# PERIPHERAL_PORT_IO.net
KiCad netlist of a schematic drawn in Altium Designer
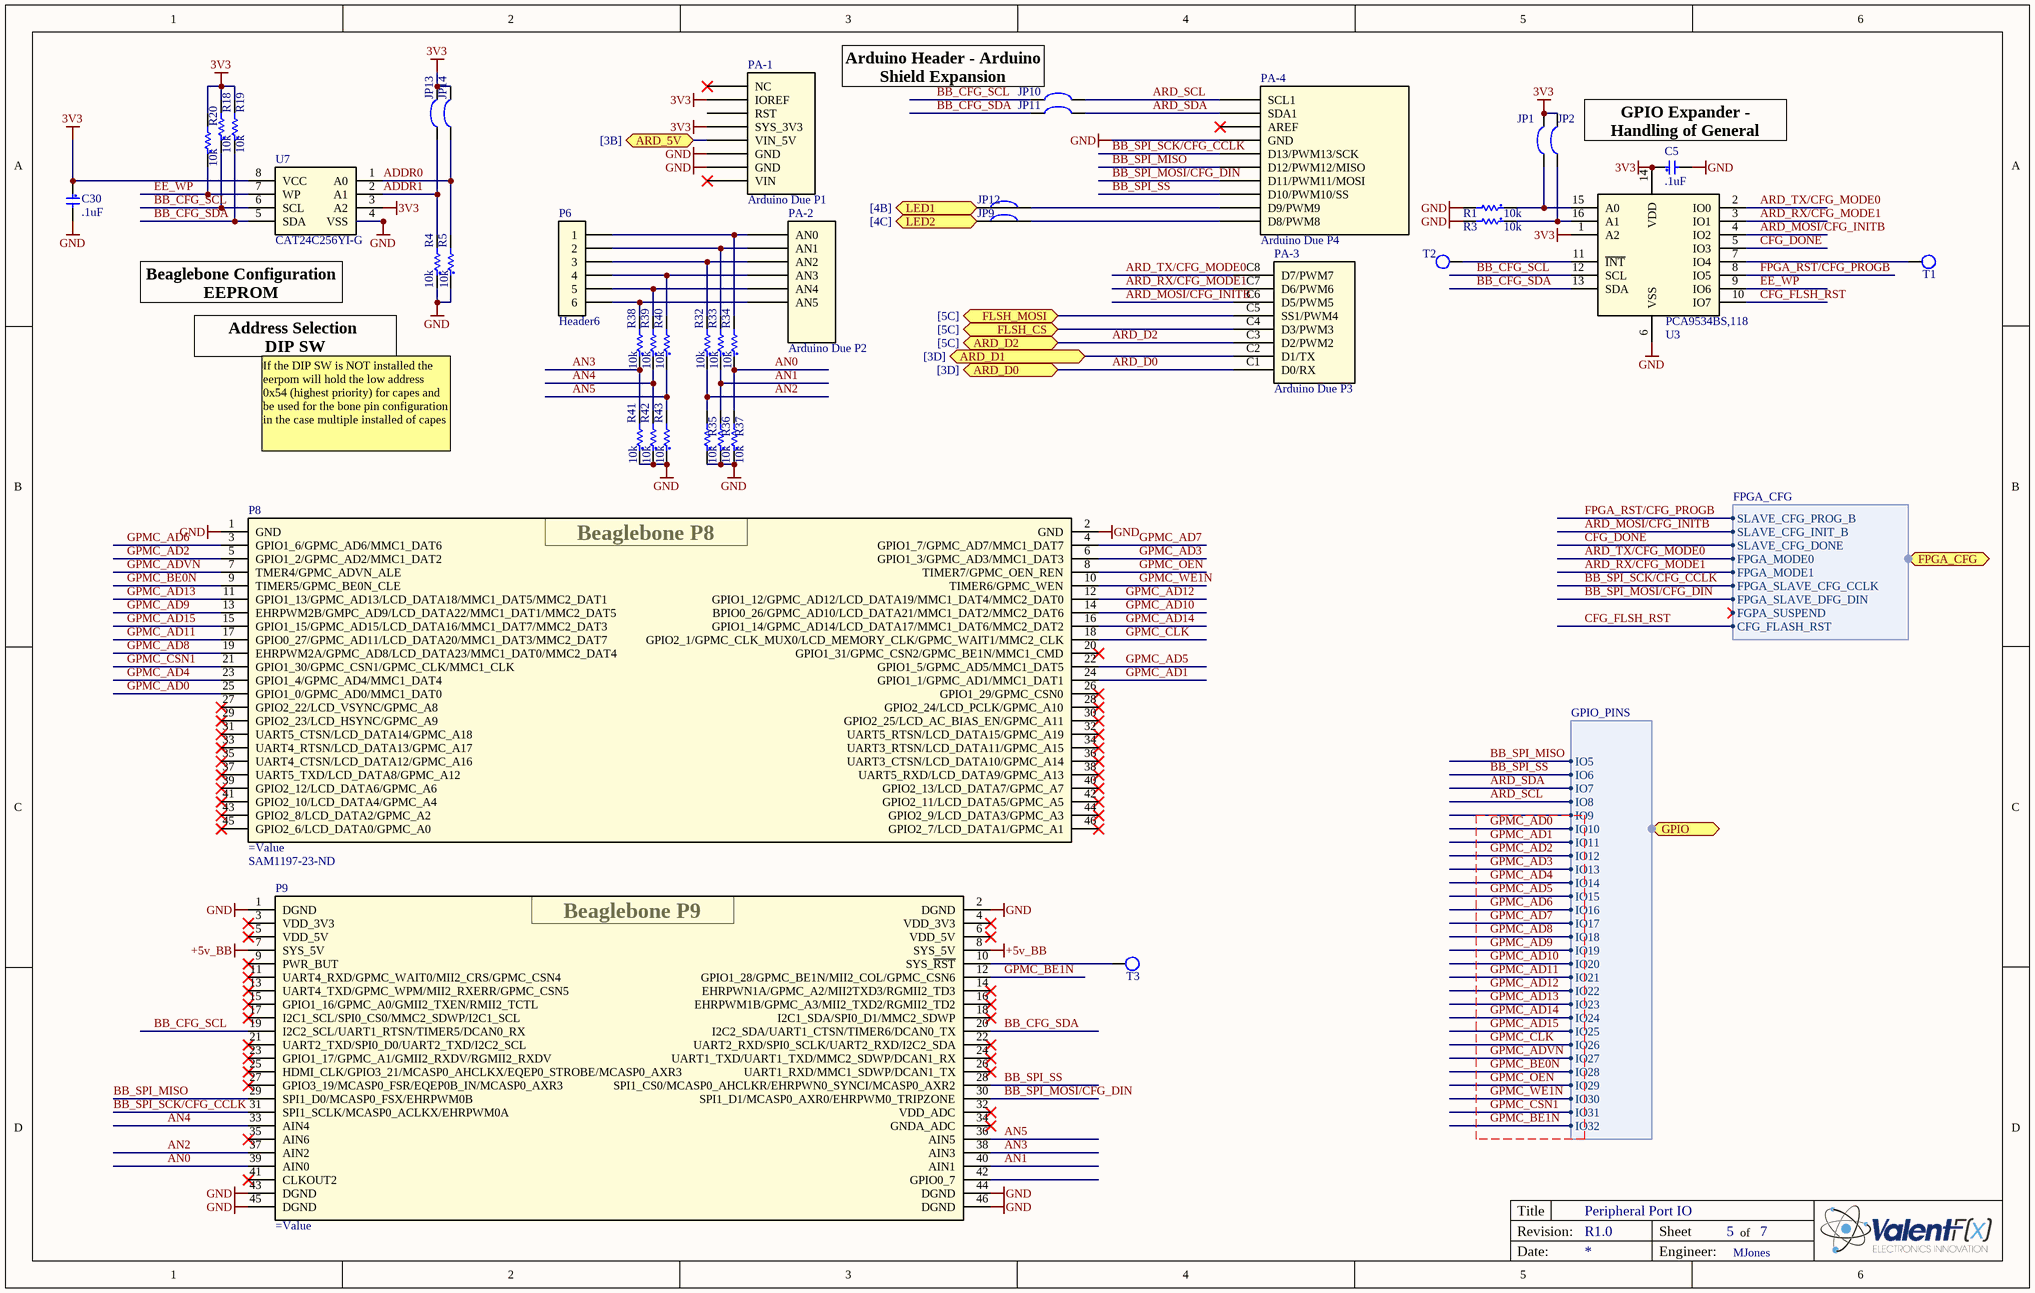
[diagram p0: PERIPHERAL_PORT_IO.SchDoc]

(export (version "E")
  (design (tool "Eeschema 10.0.6"))
  (components
    (comp (ref "C5")
      (value ".1uF")
      (footprint "c0603")
      (description "CAP CER 0.1UF 25V Y5V 0603")
      (fields
        (field (name "MANUFACTURER") "Samsung Electro-Mechanics America, Inc")
        (field (name "MANUFACTURER PART NUMBER") "CL10F104ZA8NNNC")
      )
      (libsource (lib "mCapacitors") (part "C0603 - CL10F104ZA8NNNC"))
    )
    (comp (ref "C30")
      (value ".1uF")
      (footprint "c0603")
      (description "CAP CER 0.1UF 25V Y5V 0603")
      (fields
        (field (name "MANUFACTURER") "Samsung Electro-Mechanics America, Inc")
        (field (name "MANUFACTURER PART NUMBER") "CL10F104ZA8NNNC")
      )
      (libsource (lib "") (part "C0603 - CL10F104ZA8NNNC_1"))
    )
    (comp (ref "JP1")
      (value "Solder Jumper")
      (footprint "SOLDER_JUMPER")
      (description "Solder/Configuration Jumper")
      (fields (field (name "MANUFACTURER") "n/a"))
      (libsource (lib "mConnector") (part "Solder Jumper"))
    )
    (comp (ref "JP2")
      (value "Solder Jumper")
      (footprint "SOLDER_JUMPER")
      (description "Solder/Configuration Jumper")
      (fields (field (name "MANUFACTURER") "n/a"))
      (libsource (lib "mConnector") (part "Solder Jumper"))
    )
    (comp (ref "JP9")
      (value "Solder Jumper-NC")
      (footprint "SOLDER_JUMPER-NC")
      (description "Solder/Configuration Jumper")
      (fields (field (name "MANUFACTURER") "n/a"))
      (libsource (lib "mConnector") (part "Solder Jumper-NC"))
    )
    (comp (ref "JP10")
      (value "Solder Jumper")
      (footprint "SOLDER_JUMPER")
      (description "Solder/Configuration Jumper")
      (fields (field (name "MANUFACTURER") "n/a"))
      (libsource (lib "") (part "Solder Jumper_1"))
    )
    (comp (ref "JP11")
      (value "Solder Jumper")
      (footprint "SOLDER_JUMPER")
      (description "Solder/Configuration Jumper")
      (fields (field (name "MANUFACTURER") "n/a"))
      (libsource (lib "") (part "Solder Jumper_1"))
    )
    (comp (ref "JP12")
      (value "Solder Jumper-NC")
      (footprint "SOLDER_JUMPER-NC")
      (description "Solder/Configuration Jumper")
      (fields (field (name "MANUFACTURER") "n/a"))
      (libsource (lib "mConnector") (part "Solder Jumper-NC"))
    )
    (comp (ref "JP13")
      (value "Solder Jumper")
      (footprint "SOLDER_JUMPER")
      (description "Solder/Configuration Jumper")
      (fields (field (name "MANUFACTURER") "n/a"))
      (libsource (lib "mConnector") (part "Solder Jumper"))
    )
    (comp (ref "JP14")
      (value "Solder Jumper")
      (footprint "SOLDER_JUMPER")
      (description "Solder/Configuration Jumper")
      (fields (field (name "MANUFACTURER") "n/a"))
      (libsource (lib "mConnector") (part "Solder Jumper"))
    )
    (comp (ref "P6")
      (value "Header6")
      (footprint "HEADER_6_40_100 THRU SIP")
      (description "Header 6 pin")
      (libsource (lib "mConnector") (part "Header6"))
    )
    (comp (ref "P8")
      (value "~")
      (footprint "Beaglebone-SSQ")
      (description "Beagle_Bone_Black_P8")
      (fields
        (field (name "MANUFACTURER") "Samtec Inc")
        (field (name "MANUFACTURER PART NUMBER") "SSQ-123-03-G-D-RA")
        (field (name "SUPPLIER PART NUMBER 1") "SAM1197-23-ND")
      )
      (libsource (lib "mConnector") (part "Beagle_Bone_Black_P8-SSQ"))
    )
    (comp (ref "P9")
      (value "~")
      (footprint "Beaglebone-SSQ")
      (description "Beagle_Bone_Black_P9")
      (fields
        (field (name "MANUFACTURER") "Samtec Inc")
        (field (name "MANUFACTURER PART NUMBER") "SSQ-123-03-G-D-RA")
      )
      (libsource (lib "mConnector") (part "Beagle_Bone_Black_P9-SSQ"))
    )
    (comp (ref "PA-1")
      (value "Arduino Due P1")
      (footprint "Arduino Due P1")
      (description "CONN HEADER FEMALE 8POS .1\" GOLD")
      (fields
        (field (name "MANUFACTURER") "Sullins Connector Solutions")
        (field (name "MANUFACTURER PART NUMBER") "PPPC081LFBN-RC")
      )
      (libsource (lib "mConnector") (part "Arduino Due P1"))
    )
    (comp (ref "PA-2")
      (value "Arduino Due P2")
      (footprint "Arduino Due P2")
      (description "CONN HEADER FEMALE 6POS .1\" GOLD")
      (fields
        (field (name "MANUFACTURER") "Sullins Connector Solutions")
        (field (name "MANUFACTURER PART NUMBER") "PPPC061LFBN-RC")
      )
      (libsource (lib "mConnector") (part "Arduino Due P2"))
    )
    (comp (ref "PA-3")
      (value "Arduino Due P3")
      (footprint "Arduino Due P3")
      (description "CONN HEADER FEMALE 8POS .1\" GOLD")
      (fields
        (field (name "MANUFACTURER") "Sullins Connector Solutions")
        (field (name "MANUFACTURER PART NUMBER") "PPPC081LFBN-RC")
      )
      (libsource (lib "mConnector") (part "Arduino Due P3"))
    )
    (comp (ref "PA-4")
      (value "Arduino Due P4")
      (footprint "Arduino Due P4")
      (description "CONN HEADER FMALE 10POS .1\" GOLD")
      (fields
        (field (name "MANUFACTURER") "Sullins Connector Solutions")
        (field (name "MANUFACTURER PART NUMBER") "PPPC101LFBN-RC")
      )
      (libsource (lib "mConnector") (part "Arduino Due P4"))
    )
    (comp (ref "R1")
      (value "10k")
      (footprint "mRCL:R0603")
      (description "10k Thick Film Resistors - SMD 1/10watt 10Kohms 1%")
      (fields
        (field (name "MANUFACTURER") "Vishay Dale")
        (field (name "MANUFACTURER PART NUMBER") "CRCW060310K0FKEA")
      )
      (libsource (lib "mResistors") (part "R0603 - CRCW060310K0FKEA"))
    )
    (comp (ref "R3")
      (value "10k")
      (footprint "mRCL:R0603")
      (description "10k Thick Film Resistors - SMD 1/10watt 10Kohms 1%")
      (fields
        (field (name "MANUFACTURER") "Vishay Dale")
        (field (name "MANUFACTURER PART NUMBER") "CRCW060310K0FKEA")
      )
      (libsource (lib "mResistors") (part "R0603 - CRCW060310K0FKEA"))
    )
    (comp (ref "R4")
      (value "10k")
      (footprint "mRCL:R0603")
      (description "10k Thick Film Resistors - SMD 1/10watt 10Kohms 1%")
      (fields
        (field (name "MANUFACTURER") "Vishay Dale")
        (field (name "MANUFACTURER PART NUMBER") "CRCW060310K0FKEA")
      )
      (libsource (lib "mResistors") (part "R0603 - CRCW060310K0FKEA"))
    )
    (comp (ref "R5")
      (value "10k")
      (footprint "mRCL:R0603")
      (description "10k Thick Film Resistors - SMD 1/10watt 10Kohms 1%")
      (fields
        (field (name "MANUFACTURER") "Vishay Dale")
        (field (name "MANUFACTURER PART NUMBER") "CRCW060310K0FKEA")
      )
      (libsource (lib "mResistors") (part "R0603 - CRCW060310K0FKEA"))
    )
    (comp (ref "R18")
      (value "10k")
      (footprint "mRCL:R0603")
      (description "10k Thick Film Resistors - SMD 1/10watt 10Kohms 1%")
      (fields
        (field (name "MANUFACTURER") "Vishay Dale")
        (field (name "MANUFACTURER PART NUMBER") "CRCW060310K0FKEA")
      )
      (libsource (lib "mResistors") (part "R0603 - CRCW060310K0FKEA"))
    )
    (comp (ref "R19")
      (value "10k")
      (footprint "mRCL:R0603")
      (description "10k Thick Film Resistors - SMD 1/10watt 10Kohms 1%")
      (fields
        (field (name "MANUFACTURER") "Vishay Dale")
        (field (name "MANUFACTURER PART NUMBER") "CRCW060310K0FKEA")
      )
      (libsource (lib "mResistors") (part "R0603 - CRCW060310K0FKEA"))
    )
    (comp (ref "R20")
      (value "10k")
      (footprint "mRCL:R0603")
      (description "10k Thick Film Resistors - SMD 1/10watt 10Kohms 1%")
      (fields
        (field (name "MANUFACTURER") "Vishay Dale")
        (field (name "MANUFACTURER PART NUMBER") "CRCW060310K0FKEA")
      )
      (libsource (lib "mResistors") (part "R0603 - CRCW060310K0FKEA"))
    )
    (comp (ref "R32")
      (value "10k")
      (footprint "mRCL:R0603")
      (description "10k Thick Film Resistors - SMD 1/10watt 10Kohms 1%")
      (fields
        (field (name "MANUFACTURER") "Vishay Dale")
        (field (name "MANUFACTURER PART NUMBER") "CRCW060310K0FKEA")
      )
      (libsource (lib "mResistors") (part "R0603 - CRCW060310K0FKEA"))
    )
    (comp (ref "R33")
      (value "10k")
      (footprint "mRCL:R0603")
      (description "10k Thick Film Resistors - SMD 1/10watt 10Kohms 1%")
      (fields
        (field (name "MANUFACTURER") "Vishay Dale")
        (field (name "MANUFACTURER PART NUMBER") "CRCW060310K0FKEA")
      )
      (libsource (lib "mResistors") (part "R0603 - CRCW060310K0FKEA"))
    )
    (comp (ref "R34")
      (value "10k")
      (footprint "mRCL:R0603")
      (description "10k Thick Film Resistors - SMD 1/10watt 10Kohms 1%")
      (fields
        (field (name "MANUFACTURER") "Vishay Dale")
        (field (name "MANUFACTURER PART NUMBER") "CRCW060310K0FKEA")
      )
      (libsource (lib "mResistors") (part "R0603 - CRCW060310K0FKEA"))
    )
    (comp (ref "R35")
      (value "10k")
      (footprint "mRCL:R0603")
      (description "10k Thick Film Resistors - SMD 1/10watt 10Kohms 1%")
      (fields
        (field (name "MANUFACTURER") "Vishay Dale")
        (field (name "MANUFACTURER PART NUMBER") "CRCW060310K0FKEA")
      )
      (libsource (lib "mResistors") (part "R0603 - CRCW060310K0FKEA"))
    )
    (comp (ref "R36")
      (value "10k")
      (footprint "mRCL:R0603")
      (description "10k Thick Film Resistors - SMD 1/10watt 10Kohms 1%")
      (fields
        (field (name "MANUFACTURER") "Vishay Dale")
        (field (name "MANUFACTURER PART NUMBER") "CRCW060310K0FKEA")
      )
      (libsource (lib "mResistors") (part "R0603 - CRCW060310K0FKEA"))
    )
    (comp (ref "R37")
      (value "10k")
      (footprint "mRCL:R0603")
      (description "10k Thick Film Resistors - SMD 1/10watt 10Kohms 1%")
      (fields
        (field (name "MANUFACTURER") "Vishay Dale")
        (field (name "MANUFACTURER PART NUMBER") "CRCW060310K0FKEA")
      )
      (libsource (lib "mResistors") (part "R0603 - CRCW060310K0FKEA"))
    )
    (comp (ref "R38")
      (value "10k")
      (footprint "mRCL:R0603")
      (description "10k Thick Film Resistors - SMD 1/10watt 10Kohms 1%")
      (fields
        (field (name "MANUFACTURER") "Vishay Dale")
        (field (name "MANUFACTURER PART NUMBER") "CRCW060310K0FKEA")
      )
      (libsource (lib "mResistors") (part "R0603 - CRCW060310K0FKEA"))
    )
    (comp (ref "R39")
      (value "10k")
      (footprint "mRCL:R0603")
      (description "10k Thick Film Resistors - SMD 1/10watt 10Kohms 1%")
      (fields
        (field (name "MANUFACTURER") "Vishay Dale")
        (field (name "MANUFACTURER PART NUMBER") "CRCW060310K0FKEA")
      )
      (libsource (lib "mResistors") (part "R0603 - CRCW060310K0FKEA"))
    )
    (comp (ref "R40")
      (value "10k")
      (footprint "mRCL:R0603")
      (description "10k Thick Film Resistors - SMD 1/10watt 10Kohms 1%")
      (fields
        (field (name "MANUFACTURER") "Vishay Dale")
        (field (name "MANUFACTURER PART NUMBER") "CRCW060310K0FKEA")
      )
      (libsource (lib "mResistors") (part "R0603 - CRCW060310K0FKEA"))
    )
    (comp (ref "R41")
      (value "10k")
      (footprint "mRCL:R0603")
      (description "10k Thick Film Resistors - SMD 1/10watt 10Kohms 1%")
      (fields
        (field (name "MANUFACTURER") "Vishay Dale")
        (field (name "MANUFACTURER PART NUMBER") "CRCW060310K0FKEA")
      )
      (libsource (lib "mResistors") (part "R0603 - CRCW060310K0FKEA"))
    )
    (comp (ref "R42")
      (value "10k")
      (footprint "mRCL:R0603")
      (description "10k Thick Film Resistors - SMD 1/10watt 10Kohms 1%")
      (fields
        (field (name "MANUFACTURER") "Vishay Dale")
        (field (name "MANUFACTURER PART NUMBER") "CRCW060310K0FKEA")
      )
      (libsource (lib "mResistors") (part "R0603 - CRCW060310K0FKEA"))
    )
    (comp (ref "R43")
      (value "10k")
      (footprint "mRCL:R0603")
      (description "10k Thick Film Resistors - SMD 1/10watt 10Kohms 1%")
      (fields
        (field (name "MANUFACTURER") "Vishay Dale")
        (field (name "MANUFACTURER PART NUMBER") "CRCW060310K0FKEA")
      )
      (libsource (lib "mResistors") (part "R0603 - CRCW060310K0FKEA"))
    )
    (comp (ref "T1")
      (value "Test Point")
      (footprint "Tp 25-40")
      (description "Test Point Smaller Symbol")
      (libsource (lib "mConnector") (part "Test Point 2"))
    )
    (comp (ref "T2")
      (value "Test Point")
      (footprint "Tp 25-40")
      (description "Test Point Smaller Symbol")
      (libsource (lib "mConnector") (part "Test Point 2"))
    )
    (comp (ref "T3")
      (value "Test Point")
      (footprint "Tp 25-40")
      (description "Test Point Smaller Symbol")
      (libsource (lib "mConnector") (part "Test Point 2"))
    )
    (comp (ref "U3")
      (value "PCA9534BS,118")
      (footprint "EXP - PCA9534BS,118 - QFN65P400X400X100-16M")
      (description "I/O Expanders, Repeaters & Hubs 8BIT I2C/SMBUS I/O")
      (fields (field (name "MANUFACTURER") "NXP Semiconductors"))
      (libsource (lib "mIC") (part "EXP - PCA9534BS,118"))
    )
    (comp (ref "U7")
      (value "CAT24C256YI-G")
      (footprint "TSSOP 8")
      (description "IC EEPROM 256KBIT 400KHZ 8TSSOP")
      (fields (field (name "MANUFACTURER") "ON Semiconductor"))
      (libsource (lib "mIC") (part "EEPROM - CAT24C256YI-G"))
    )
  )
  (nets
    (net (code "3") (name "+5v_BB") (class "Default")
      (node (ref "P9") (pin "7") (pinfunction "SYS_5V_7") (pintype "passive"))
      (node (ref "P9") (pin "8") (pinfunction "SYS_5V_8") (pintype "passive"))
    )
    (net (code "4") (name "/ADDR0") (class "Default")
      (node (ref "JP14") (pin "1") (pinfunction "1_1") (pintype "passive"))
      (node (ref "R5") (pin "2") (pinfunction "2_2") (pintype "passive"))
      (node (ref "U7") (pin "1") (pinfunction "A0_1") (pintype "passive"))
    )
    (net (code "5") (name "/ADDR1") (class "Default")
      (node (ref "JP13") (pin "1") (pinfunction "1_1") (pintype "passive"))
      (node (ref "R4") (pin "2") (pinfunction "2_2") (pintype "passive"))
      (node (ref "U7") (pin "2") (pinfunction "A1_2") (pintype "passive"))
    )
    (net (code "6") (name "/AN0") (class "Default")
      (node (ref "P9") (pin "39") (pinfunction "AIN0_39") (pintype "passive"))
      (node (ref "R34") (pin "1") (pinfunction "1_1") (pintype "passive"))
      (node (ref "R37") (pin "2") (pinfunction "2_2") (pintype "passive"))
    )
    (net (code "7") (name "/AN1") (class "Default")
      (node (ref "P9") (pin "40") (pinfunction "AIN1_40") (pintype "passive"))
      (node (ref "R33") (pin "1") (pinfunction "1_1") (pintype "passive"))
      (node (ref "R36") (pin "2") (pinfunction "2_2") (pintype "passive"))
    )
    (net (code "8") (name "/AN2") (class "Default")
      (node (ref "P9") (pin "37") (pinfunction "AIN2_37") (pintype "passive"))
      (node (ref "R32") (pin "1") (pinfunction "1_1") (pintype "passive"))
      (node (ref "R35") (pin "2") (pinfunction "2_2") (pintype "passive"))
    )
    (net (code "9") (name "/AN3") (class "Default")
      (node (ref "P9") (pin "38") (pinfunction "AIN3_38") (pintype "passive"))
      (node (ref "R38") (pin "1") (pinfunction "1_1") (pintype "passive"))
      (node (ref "R41") (pin "2") (pinfunction "2_2") (pintype "passive"))
    )
    (net (code "10") (name "/AN4") (class "Default")
      (node (ref "P9") (pin "33") (pinfunction "AIN4_33") (pintype "passive"))
      (node (ref "R39") (pin "1") (pinfunction "1_1") (pintype "passive"))
      (node (ref "R42") (pin "2") (pinfunction "2_2") (pintype "passive"))
    )
    (net (code "11") (name "/AN5") (class "Default")
      (node (ref "P9") (pin "36") (pinfunction "AIN5_36") (pintype "passive"))
      (node (ref "R40") (pin "1") (pinfunction "1_1") (pintype "passive"))
      (node (ref "R43") (pin "2") (pinfunction "2_2") (pintype "passive"))
    )
    (net (code "12") (name "/ARD_5V") (class "Default")
      (node (ref "PA-1") (pin "A5") (pinfunction "VIN_5V_A5") (pintype "passive"))
    )
    (net (code "13") (name "/ARD_D0") (class "Default")
      (node (ref "PA-3") (pin "C1") (pinfunction "D0/RX_C1") (pintype "passive"))
    )
    (net (code "14") (name "/ARD_D1") (class "Default")
      (node (ref "PA-3") (pin "C2") (pinfunction "D1/TX_C2") (pintype "passive"))
    )
    (net (code "15") (name "/ARD_D2") (class "Default")
      (node (ref "PA-3") (pin "C3") (pinfunction "D2/PWM2_C3") (pintype "passive"))
    )
    (net (code "16") (name "/ARD_MOSI{slash}CFG_INITB") (class "Default")
      (node (ref "PA-3") (pin "C6") (pinfunction "D5/PWM5_C6") (pintype "passive"))
      (node (ref "U3") (pin "4") (pinfunction "IO2_4") (pintype "passive"))
    )
    (net (code "17") (name "/ARD_RX{slash}CFG_MODE1") (class "Default")
      (node (ref "PA-3") (pin "C7") (pinfunction "D6/PWM6_C7") (pintype "passive"))
      (node (ref "U3") (pin "3") (pinfunction "IO1_3") (pintype "passive"))
    )
    (net (code "18") (name "/ARD_SCL") (class "Default")
      (node (ref "JP10") (pin "2") (pinfunction "2_2") (pintype "passive"))
      (node (ref "PA-4") (pin "D10") (pinfunction "SCL1_D10") (pintype "passive"))
    )
    (net (code "19") (name "/ARD_SDA") (class "Default")
      (node (ref "JP11") (pin "2") (pinfunction "2_2") (pintype "passive"))
      (node (ref "PA-4") (pin "D9") (pinfunction "SDA1_D9") (pintype "passive"))
    )
    (net (code "20") (name "/ARD_TX{slash}CFG_MODE0") (class "Default")
      (node (ref "PA-3") (pin "C8") (pinfunction "D7/PWM7_C8") (pintype "passive"))
      (node (ref "U3") (pin "2") (pinfunction "IO0_2") (pintype "passive"))
    )
    (net (code "21") (name "/BB_CFG_SCL") (class "Default")
      (node (ref "JP10") (pin "1") (pinfunction "1_1") (pintype "passive"))
      (node (ref "P9") (pin "19") (pinfunction "I2C2_SCL/UART1_RTSN/TIMER5/DCAN0_RX_19") (pintype "passive"))
      (node (ref "R18") (pin "1") (pinfunction "1_1") (pintype "passive"))
      (node (ref "U3") (pin "12") (pinfunction "SCL_12") (pintype "passive"))
      (node (ref "U7") (pin "6") (pinfunction "SCL_6") (pintype "passive"))
    )
    (net (code "22") (name "/BB_CFG_SDA") (class "Default")
      (node (ref "JP11") (pin "1") (pinfunction "1_1") (pintype "passive"))
      (node (ref "P9") (pin "20") (pinfunction "I2C2_SDA/UART1_CTSN/TIMER6/DCAN0_TX_20") (pintype "passive"))
      (node (ref "R19") (pin "1") (pinfunction "1_1") (pintype "passive"))
      (node (ref "U3") (pin "13") (pinfunction "SDA_13") (pintype "passive"))
      (node (ref "U7") (pin "5") (pinfunction "SDA_5") (pintype "passive"))
    )
    (net (code "23") (name "/BB_SPI_MISO") (class "Default")
      (node (ref "P9") (pin "29") (pinfunction "SPI1_D0/MCASP0_FSX/EHRPWM0B_29") (pintype "passive"))
      (node (ref "PA-4") (pin "D5") (pinfunction "D12/PWM12/MISO_D5") (pintype "passive"))
    )
    (net (code "24") (name "/BB_SPI_MOSI{slash}CFG_DIN") (class "Default")
      (node (ref "P9") (pin "30") (pinfunction "SPI1_D1/MCASP0_AXR0/EHRPWM0_TRIPZONE_30") (pintype "passive"))
      (node (ref "PA-4") (pin "D4") (pinfunction "D11/PWM11/MOSI_D4") (pintype "passive"))
    )
    (net (code "25") (name "/BB_SPI_SCK{slash}CFG_CCLK") (class "Default")
      (node (ref "P9") (pin "31") (pinfunction "SPI1_SCLK/MCASP0_ACLKX/EHRPWM0A_31") (pintype "passive"))
      (node (ref "PA-4") (pin "D6") (pinfunction "D13/PWM13/SCK_D6") (pintype "passive"))
    )
    (net (code "26") (name "/BB_SPI_SS") (class "Default")
      (node (ref "P9") (pin "28") (pinfunction "SPI1_CS0/MCASP0_AHCLKR/EHRPWN0_SYNCI/MCASP0_AXR2_28") (pintype "passive"))
      (node (ref "PA-4") (pin "D3") (pinfunction "D10/PWM10/SS_D3") (pintype "passive"))
    )
    (net (code "27") (name "/CFG_DONE") (class "Default")
      (node (ref "U3") (pin "5") (pinfunction "IO3_5") (pintype "passive"))
    )
    (net (code "28") (name "/CFG_FLSH_RST") (class "Default")
      (node (ref "U3") (pin "10") (pinfunction "IO7_10") (pintype "passive"))
    )
    (net (code "29") (name "/EE_WP") (class "Default")
      (node (ref "R20") (pin "1") (pinfunction "1_1") (pintype "passive"))
      (node (ref "U3") (pin "9") (pinfunction "IO6_9") (pintype "passive"))
      (node (ref "U7") (pin "7") (pinfunction "WP_7") (pintype "passive"))
    )
    (net (code "30") (name "/FLSH_CS") (class "Default")
      (node (ref "PA-3") (pin "C4") (pinfunction "D3/PWM3_C4") (pintype "passive"))
    )
    (net (code "31") (name "/FLSH_MOSI") (class "Default")
      (node (ref "PA-3") (pin "C5") (pinfunction "SS1/PWM4_C5") (pintype "passive"))
    )
    (net (code "32") (name "/FPGA_RST{slash}CFG_PROGB") (class "Default")
      (node (ref "U3") (pin "8") (pinfunction "IO5_8") (pintype "passive"))
    )
    (net (code "33") (name "/GPMC_AD0") (class "Default")
      (node (ref "P8") (pin "25") (pinfunction "GPIO1_0/GPMC_AD0/MMC1_DAT0_25") (pintype "passive"))
    )
    (net (code "34") (name "/GPMC_AD1") (class "Default")
      (node (ref "P8") (pin "24") (pinfunction "GPIO1_1/GPMC_AD1/MMC1_DAT1_24") (pintype "passive"))
    )
    (net (code "35") (name "/GPMC_AD2") (class "Default")
      (node (ref "P8") (pin "5") (pinfunction "GPIO1_2/GPMC_AD2/MMC1_DAT2_5") (pintype "passive"))
    )
    (net (code "36") (name "/GPMC_AD3") (class "Default")
      (node (ref "P8") (pin "6") (pinfunction "GPIO1_3/GPMC_AD3/MMC1_DAT3_6") (pintype "passive"))
    )
    (net (code "37") (name "/GPMC_AD4") (class "Default")
      (node (ref "P8") (pin "23") (pinfunction "GPIO1_4/GPMC_AD4/MMC1_DAT4_23") (pintype "passive"))
    )
    (net (code "38") (name "/GPMC_AD5") (class "Default")
      (node (ref "P8") (pin "22") (pinfunction "GPIO1_5/GPMC_AD5/MMC1_DAT5_22") (pintype "passive"))
    )
    (net (code "39") (name "/GPMC_AD6") (class "Default")
      (node (ref "P8") (pin "3") (pinfunction "GPIO1_6/GPMC_AD6/MMC1_DAT6_3") (pintype "passive"))
    )
    (net (code "40") (name "/GPMC_AD7") (class "Default")
      (node (ref "P8") (pin "4") (pinfunction "GPIO1_7/GPMC_AD7/MMC1_DAT7_4") (pintype "passive"))
    )
    (net (code "41") (name "/GPMC_AD8") (class "Default")
      (node (ref "P8") (pin "19") (pinfunction "EHRPWM2A/GPMC_AD8/LCD_DATA23/MMC1_DAT0/MMC2_DAT4_19") (pintype "passive"))
    )
    (net (code "42") (name "/GPMC_AD9") (class "Default")
      (node (ref "P8") (pin "13") (pinfunction "EHRPWM2B/GMPC_AD9/LCD_DATA22/MMC1_DAT1/MMC2_DAT5_13") (pintype "passive"))
    )
    (net (code "43") (name "/GPMC_AD10") (class "Default")
      (node (ref "P8") (pin "14") (pinfunction "BPIO0_26/GPMC_AD10/LCD_DATA21/MMC1_DAT2/MMC2_DAT6_14") (pintype "passive"))
    )
    (net (code "44") (name "/GPMC_AD11") (class "Default")
      (node (ref "P8") (pin "17") (pinfunction "GPIO0_27/GPMC_AD11/LCD_DATA20/MMC1_DAT3/MMC2_DAT7_17") (pintype "passive"))
    )
    (net (code "45") (name "/GPMC_AD12") (class "Default")
      (node (ref "P8") (pin "12") (pinfunction "GPIO1_12/GPMC_AD12/LCD_DATA19/MMC1_DAT4/MMC2_DAT0_12") (pintype "passive"))
    )
    (net (code "46") (name "/GPMC_AD13") (class "Default")
      (node (ref "P8") (pin "11") (pinfunction "GPIO1_13/GPMC_AD13/LCD_DATA18/MMC1_DAT5/MMC2_DAT1_11") (pintype "passive"))
    )
    (net (code "47") (name "/GPMC_AD14") (class "Default")
      (node (ref "P8") (pin "16") (pinfunction "GPIO1_14/GPMC_AD14/LCD_DATA17/MMC1_DAT6/MMC2_DAT2_16") (pintype "passive"))
    )
    (net (code "48") (name "/GPMC_AD15") (class "Default")
      (node (ref "P8") (pin "15") (pinfunction "GPIO1_15/GPMC_AD15/LCD_DATA16/MMC1_DAT7/MMC2_DAT3_15") (pintype "passive"))
    )
    (net (code "49") (name "/GPMC_ADVN") (class "Default")
      (node (ref "P8") (pin "7") (pinfunction "TMER4/GPMC_ADVN_ALE_7") (pintype "passive"))
    )
    (net (code "50") (name "/GPMC_BE0N") (class "Default")
      (node (ref "P8") (pin "9") (pinfunction "TIMER5/GPMC_BE0N_CLE_9") (pintype "passive"))
    )
    (net (code "51") (name "/GPMC_BE1N") (class "Default")
      (node (ref "P9") (pin "12") (pinfunction "GPIO1_28/GPMC_BE1N/MII2_COL/GPMC_CSN6_12") (pintype "passive"))
    )
    (net (code "52") (name "/GPMC_CLK") (class "Default")
      (node (ref "P8") (pin "18") (pinfunction "GPIO2_1/GPMC_CLK_MUX0/LCD_MEMORY_CLK/GPMC_WAIT1/MMC2_CLK_18") (pintype "passive"))
    )
    (net (code "53") (name "/GPMC_CSN1") (class "Default")
      (node (ref "P8") (pin "21") (pinfunction "GPIO1_30/GPMC_CSN1/GPMC_CLK/MMC1_CLK_21") (pintype "passive"))
    )
    (net (code "54") (name "/GPMC_OEN") (class "Default")
      (node (ref "P8") (pin "8") (pinfunction "TIMER7/GPMC_OEN_REN_8") (pintype "passive"))
    )
    (net (code "55") (name "/GPMC_WE1N") (class "Default")
      (node (ref "P8") (pin "10") (pinfunction "TIMER6/GPMC_WEN_10") (pintype "passive"))
    )
    (net (code "56") (name "/LED1") (class "Default")
      (node (ref "JP12") (pin "1") (pinfunction "1_1") (pintype "passive"))
    )
    (net (code "57") (name "/LED2") (class "Default")
      (node (ref "JP9") (pin "1") (pinfunction "1_1") (pintype "passive"))
    )
    (net (code "60") (name "3V3") (class "Default")
      (node (ref "C30") (pin "1") (pinfunction "1_1") (pintype "passive"))
      (node (ref "C5") (pin "1") (pinfunction "1_1") (pintype "passive"))
      (node (ref "JP1") (pin "2") (pinfunction "2_2") (pintype "passive"))
      (node (ref "JP13") (pin "2") (pinfunction "2_2") (pintype "passive"))
      (node (ref "JP14") (pin "2") (pinfunction "2_2") (pintype "passive"))
      (node (ref "JP2") (pin "2") (pinfunction "2_2") (pintype "passive"))
      (node (ref "PA-1") (pin "A2") (pinfunction "IOREF_A2") (pintype "passive"))
      (node (ref "PA-1") (pin "A4") (pinfunction "SYS_3V3_A4") (pintype "passive"))
      (node (ref "R18") (pin "2") (pinfunction "2_2") (pintype "passive"))
      (node (ref "R19") (pin "2") (pinfunction "2_2") (pintype "passive"))
      (node (ref "R20") (pin "2") (pinfunction "2_2") (pintype "passive"))
      (node (ref "U3") (pin "1") (pinfunction "A2_1") (pintype "passive"))
      (node (ref "U3") (pin "14") (pinfunction "VDD_14") (pintype "passive"))
      (node (ref "U7") (pin "3") (pinfunction "A2_3") (pintype "passive"))
      (node (ref "U7") (pin "8") (pinfunction "VCC_8") (pintype "passive"))
    )
    (net (code "61") (name "GND") (class "Default")
      (node (ref "C30") (pin "2") (pinfunction "2_2") (pintype "passive"))
      (node (ref "C5") (pin "2") (pinfunction "2_2") (pintype "passive"))
      (node (ref "P8") (pin "1") (pinfunction "GND_1") (pintype "passive"))
      (node (ref "P8") (pin "2") (pinfunction "GND_2") (pintype "passive"))
      (node (ref "P9") (pin "1") (pinfunction "DGND_1") (pintype "passive"))
      (node (ref "P9") (pin "2") (pinfunction "DGND_2") (pintype "passive"))
      (node (ref "P9") (pin "43") (pinfunction "DGND_43") (pintype "passive"))
      (node (ref "P9") (pin "44") (pinfunction "DGND_44") (pintype "passive"))
      (node (ref "P9") (pin "45") (pinfunction "DGND_45") (pintype "passive"))
      (node (ref "P9") (pin "46") (pinfunction "DGND_46") (pintype "passive"))
      (node (ref "PA-1") (pin "A6") (pinfunction "GND_A6") (pintype "passive"))
      (node (ref "PA-1") (pin "A7") (pinfunction "GND_A7") (pintype "passive"))
      (node (ref "PA-4") (pin "D7") (pinfunction "GND_D7") (pintype "passive"))
      (node (ref "R1") (pin "2") (pinfunction "2_2") (pintype "passive"))
      (node (ref "R3") (pin "2") (pinfunction "2_2") (pintype "passive"))
      (node (ref "R35") (pin "1") (pinfunction "1_1") (pintype "passive"))
      (node (ref "R36") (pin "1") (pinfunction "1_1") (pintype "passive"))
      (node (ref "R37") (pin "1") (pinfunction "1_1") (pintype "passive"))
      (node (ref "R4") (pin "1") (pinfunction "1_1") (pintype "passive"))
      (node (ref "R41") (pin "1") (pinfunction "1_1") (pintype "passive"))
      (node (ref "R42") (pin "1") (pinfunction "1_1") (pintype "passive"))
      (node (ref "R43") (pin "1") (pinfunction "1_1") (pintype "passive"))
      (node (ref "R5") (pin "1") (pinfunction "1_1") (pintype "passive"))
      (node (ref "U3") (pin "6") (pinfunction "VSS_6") (pintype "passive"))
      (node (ref "U7") (pin "4") (pinfunction "VSS_4") (pintype "passive"))
    )
    (net (code "62") (name "Net-(P9-SYS_~{RST})") (class "Default")
      (node (ref "P9") (pin "10") (pinfunction "SYS_~{RST}_10") (pintype "passive"))
      (node (ref "T3") (pin "1") (pinfunction "1_1") (pintype "passive"))
    )
    (net (code "63") (name "Net-(PA-2-AN0)") (class "Default")
      (node (ref "P6") (pin "1") (pinfunction "1_1") (pintype "passive"))
      (node (ref "PA-2") (pin "B1") (pinfunction "AN0_B1") (pintype "passive"))
      (node (ref "R34") (pin "2") (pinfunction "2_2") (pintype "passive"))
    )
    (net (code "64") (name "Net-(PA-2-AN1)") (class "Default")
      (node (ref "P6") (pin "2") (pinfunction "2_2") (pintype "passive"))
      (node (ref "PA-2") (pin "B2") (pinfunction "AN1_B2") (pintype "passive"))
      (node (ref "R33") (pin "2") (pinfunction "2_2") (pintype "passive"))
    )
    (net (code "65") (name "Net-(PA-2-AN2)") (class "Default")
      (node (ref "P6") (pin "3") (pinfunction "3_3") (pintype "passive"))
      (node (ref "PA-2") (pin "B3") (pinfunction "AN2_B3") (pintype "passive"))
      (node (ref "R32") (pin "2") (pinfunction "2_2") (pintype "passive"))
    )
    (net (code "66") (name "Net-(PA-2-AN3)") (class "Default")
      (node (ref "P6") (pin "4") (pinfunction "4_4") (pintype "passive"))
      (node (ref "PA-2") (pin "B4") (pinfunction "AN3_B4") (pintype "passive"))
      (node (ref "R40") (pin "2") (pinfunction "2_2") (pintype "passive"))
    )
    (net (code "67") (name "Net-(PA-2-AN4)") (class "Default")
      (node (ref "P6") (pin "5") (pinfunction "5_5") (pintype "passive"))
      (node (ref "PA-2") (pin "B5") (pinfunction "AN4_B5") (pintype "passive"))
      (node (ref "R39") (pin "2") (pinfunction "2_2") (pintype "passive"))
    )
    (net (code "68") (name "Net-(PA-2-AN5)") (class "Default")
      (node (ref "P6") (pin "6") (pinfunction "6_6") (pintype "passive"))
      (node (ref "PA-2") (pin "B6") (pinfunction "AN5_B6") (pintype "passive"))
      (node (ref "R38") (pin "2") (pinfunction "2_2") (pintype "passive"))
    )
    (net (code "69") (name "Net-(PA-4-D8{slash}PWM8)") (class "Default")
      (node (ref "JP9") (pin "2") (pinfunction "2_2") (pintype "passive"))
      (node (ref "PA-4") (pin "D1") (pinfunction "D8/PWM8_D1") (pintype "passive"))
    )
    (net (code "70") (name "Net-(PA-4-D9{slash}PWM9)") (class "Default")
      (node (ref "JP12") (pin "2") (pinfunction "2_2") (pintype "passive"))
      (node (ref "PA-4") (pin "D2") (pinfunction "D9/PWM9_D2") (pintype "passive"))
    )
    (net (code "71") (name "Net-(U3-A0)") (class "Default")
      (node (ref "JP1") (pin "1") (pinfunction "1_1") (pintype "passive"))
      (node (ref "R1") (pin "1") (pinfunction "1_1") (pintype "passive"))
      (node (ref "U3") (pin "15") (pinfunction "A0_15") (pintype "passive"))
    )
    (net (code "72") (name "Net-(U3-A1)") (class "Default")
      (node (ref "JP2") (pin "1") (pinfunction "1_1") (pintype "passive"))
      (node (ref "R3") (pin "1") (pinfunction "1_1") (pintype "passive"))
      (node (ref "U3") (pin "16") (pinfunction "A1_16") (pintype "passive"))
    )
    (net (code "73") (name "Net-(U3-IO4)") (class "Default")
      (node (ref "T1") (pin "1") (pinfunction "1_1") (pintype "passive"))
      (node (ref "U3") (pin "7") (pinfunction "IO4_7") (pintype "passive"))
    )
    (net (code "74") (name "Net-(U3-~{INT})") (class "Default")
      (node (ref "T2") (pin "1") (pinfunction "1_1") (pintype "passive"))
      (node (ref "U3") (pin "11") (pinfunction "~{INT}_11") (pintype "passive"))
    )
    (net (code "75") (name "unconnected-(P8-GPIO1_29{slash}GPMC_CSN0-Pad26)") (class "Default")
      (node (ref "P8") (pin "26") (pinfunction "GPIO1_29/GPMC_CSN0_26") (pintype "passive+no_connect"))
    )
    (net (code "76") (name "unconnected-(P8-GPIO1_31{slash}GPMC_CSN2{slash}GPMC_BE1N{slash}MMC1_CMD-Pad20)") (class "Default")
      (node (ref "P8") (pin "20") (pinfunction "GPIO1_31/GPMC_CSN2/GPMC_BE1N/MMC1_CMD_20") (pintype "passive+no_connect"))
    )
    (net (code "77") (name "unconnected-(P8-GPIO2_6{slash}LCD_DATA0{slash}GPMC_A0-Pad45)") (class "Default")
      (node (ref "P8") (pin "45") (pinfunction "GPIO2_6/LCD_DATA0/GPMC_A0_45") (pintype "passive+no_connect"))
    )
    (net (code "78") (name "unconnected-(P8-GPIO2_7{slash}LCD_DATA1{slash}GPMC_A1-Pad46)") (class "Default")
      (node (ref "P8") (pin "46") (pinfunction "GPIO2_7/LCD_DATA1/GPMC_A1_46") (pintype "passive+no_connect"))
    )
    (net (code "79") (name "unconnected-(P8-GPIO2_8{slash}LCD_DATA2{slash}GPMC_A2-Pad43)") (class "Default")
      (node (ref "P8") (pin "43") (pinfunction "GPIO2_8/LCD_DATA2/GPMC_A2_43") (pintype "passive+no_connect"))
    )
    (net (code "80") (name "unconnected-(P8-GPIO2_9{slash}LCD_DATA3{slash}GPMC_A3-Pad44)") (class "Default")
      (node (ref "P8") (pin "44") (pinfunction "GPIO2_9/LCD_DATA3/GPMC_A3_44") (pintype "passive+no_connect"))
    )
    (net (code "81") (name "unconnected-(P8-GPIO2_10{slash}LCD_DATA4{slash}GPMC_A4-Pad41)") (class "Default")
      (node (ref "P8") (pin "41") (pinfunction "GPIO2_10/LCD_DATA4/GPMC_A4_41") (pintype "passive+no_connect"))
    )
    (net (code "82") (name "unconnected-(P8-GPIO2_11{slash}LCD_DATA5{slash}GPMC_A5-Pad42)") (class "Default")
      (node (ref "P8") (pin "42") (pinfunction "GPIO2_11/LCD_DATA5/GPMC_A5_42") (pintype "passive+no_connect"))
    )
    (net (code "83") (name "unconnected-(P8-GPIO2_12{slash}LCD_DATA6{slash}GPMC_A6-Pad39)") (class "Default")
      (node (ref "P8") (pin "39") (pinfunction "GPIO2_12/LCD_DATA6/GPMC_A6_39") (pintype "passive+no_connect"))
    )
    (net (code "84") (name "unconnected-(P8-GPIO2_13{slash}LCD_DATA7{slash}GPMC_A7-Pad40)") (class "Default")
      (node (ref "P8") (pin "40") (pinfunction "GPIO2_13/LCD_DATA7/GPMC_A7_40") (pintype "passive+no_connect"))
    )
    (net (code "85") (name "unconnected-(P8-GPIO2_22{slash}LCD_VSYNC{slash}GPMC_A8-Pad27)") (class "Default")
      (node (ref "P8") (pin "27") (pinfunction "GPIO2_22/LCD_VSYNC/GPMC_A8_27") (pintype "passive+no_connect"))
    )
    (net (code "86") (name "unconnected-(P8-GPIO2_23{slash}LCD_HSYNC{slash}GPMC_A9-Pad29)") (class "Default")
      (node (ref "P8") (pin "29") (pinfunction "GPIO2_23/LCD_HSYNC/GPMC_A9_29") (pintype "passive+no_connect"))
    )
    (net (code "87") (name "unconnected-(P8-GPIO2_24{slash}LCD_PCLK{slash}GPMC_A10-Pad28)") (class "Default")
      (node (ref "P8") (pin "28") (pinfunction "GPIO2_24/LCD_PCLK/GPMC_A10_28") (pintype "passive+no_connect"))
    )
    (net (code "88") (name "unconnected-(P8-GPIO2_25{slash}LCD_AC_BIAS_EN{slash}GPMC_A11-Pad30)") (class "Default")
      (node (ref "P8") (pin "30") (pinfunction "GPIO2_25/LCD_AC_BIAS_EN/GPMC_A11_30") (pintype "passive+no_connect"))
    )
    (net (code "89") (name "unconnected-(P8-UART3_CTSN{slash}LCD_DATA10{slash}GPMC_A14-Pad36)") (class "Default")
      (node (ref "P8") (pin "36") (pinfunction "UART3_CTSN/LCD_DATA10/GPMC_A14_36") (pintype "passive+no_connect"))
    )
    (net (code "90") (name "unconnected-(P8-UART3_RTSN{slash}LCD_DATA11{slash}GPMC_A15-Pad34)") (class "Default")
      (node (ref "P8") (pin "34") (pinfunction "UART3_RTSN/LCD_DATA11/GPMC_A15_34") (pintype "passive+no_connect"))
    )
    (net (code "91") (name "unconnected-(P8-UART4_CTSN{slash}LCD_DATA12{slash}GPMC_A16-Pad35)") (class "Default")
      (node (ref "P8") (pin "35") (pinfunction "UART4_CTSN/LCD_DATA12/GPMC_A16_35") (pintype "passive+no_connect"))
    )
    (net (code "92") (name "unconnected-(P8-UART4_RTSN{slash}LCD_DATA13{slash}GPMC_A17-Pad33)") (class "Default")
      (node (ref "P8") (pin "33") (pinfunction "UART4_RTSN/LCD_DATA13/GPMC_A17_33") (pintype "passive+no_connect"))
    )
    (net (code "93") (name "unconnected-(P8-UART5_CTSN{slash}LCD_DATA14{slash}GPMC_A18-Pad31)") (class "Default")
      (node (ref "P8") (pin "31") (pinfunction "UART5_CTSN/LCD_DATA14/GPMC_A18_31") (pintype "passive+no_connect"))
    )
    (net (code "94") (name "unconnected-(P8-UART5_RTSN{slash}LCD_DATA15{slash}GPMC_A19-Pad32)") (class "Default")
      (node (ref "P8") (pin "32") (pinfunction "UART5_RTSN/LCD_DATA15/GPMC_A19_32") (pintype "passive+no_connect"))
    )
    (net (code "95") (name "unconnected-(P8-UART5_RXD{slash}LCD_DATA9{slash}GPMC_A13-Pad38)") (class "Default")
      (node (ref "P8") (pin "38") (pinfunction "UART5_RXD/LCD_DATA9/GPMC_A13_38") (pintype "passive+no_connect"))
    )
    (net (code "96") (name "unconnected-(P8-UART5_TXD{slash}LCD_DATA8{slash}GPMC_A12-Pad37)") (class "Default")
      (node (ref "P8") (pin "37") (pinfunction "UART5_TXD/LCD_DATA8/GPMC_A12_37") (pintype "passive+no_connect"))
    )
    (net (code "97") (name "unconnected-(P9-AIN6-Pad35)") (class "Default")
      (node (ref "P9") (pin "35") (pinfunction "AIN6_35") (pintype "passive+no_connect"))
    )
    (net (code "98") (name "unconnected-(P9-CLKOUT2-Pad41)") (class "Default")
      (node (ref "P9") (pin "41") (pinfunction "CLKOUT2_41") (pintype "passive+no_connect"))
    )
    (net (code "99") (name "unconnected-(P9-EHRPWM1B{slash}GPMC_A3{slash}MII2_TXD2{slash}RGMII2_TD2-Pad16)") (class "Default")
      (node (ref "P9") (pin "16") (pinfunction "EHRPWM1B/GPMC_A3/MII2_TXD2/RGMII2_TD2_16") (pintype "passive+no_connect"))
    )
    (net (code "100") (name "unconnected-(P9-EHRPWN1A{slash}GPMC_A2{slash}MII2TXD3{slash}RGMII2_TD3-Pad14)") (class "Default")
      (node (ref "P9") (pin "14") (pinfunction "EHRPWN1A/GPMC_A2/MII2TXD3/RGMII2_TD3_14") (pintype "passive+no_connect"))
    )
    (net (code "101") (name "unconnected-(P9-GNDA_ADC-Pad34)") (class "Default")
      (node (ref "P9") (pin "34") (pinfunction "GNDA_ADC_34") (pintype "passive+no_connect"))
    )
    (net (code "102") (name "unconnected-(P9-GPIO0_7-Pad42)") (class "Default")
      (node (ref "P9") (pin "42") (pinfunction "GPIO0_7_42") (pintype "passive"))
    )
    (net (code "103") (name "unconnected-(P9-GPIO1_16{slash}GPMC_A0{slash}GMII2_TXEN{slash}RMII2_TCTL-Pad15)") (class "Default")
      (node (ref "P9") (pin "15") (pinfunction "GPIO1_16/GPMC_A0/GMII2_TXEN/RMII2_TCTL_15") (pintype "passive+no_connect"))
    )
    (net (code "104") (name "unconnected-(P9-GPIO1_17{slash}GPMC_A1{slash}GMII2_RXDV{slash}RGMII2_RXDV-Pad23)") (class "Default")
      (node (ref "P9") (pin "23") (pinfunction "GPIO1_17/GPMC_A1/GMII2_RXDV/RGMII2_RXDV_23") (pintype "passive+no_connect"))
    )
    (net (code "105") (name "unconnected-(P9-GPIO3_19{slash}MCASP0_FSR{slash}EQEP0B_IN{slash}MCASP0_AXR3-Pad27)") (class "Default")
      (node (ref "P9") (pin "27") (pinfunction "GPIO3_19/MCASP0_FSR/EQEP0B_IN/MCASP0_AXR3_27") (pintype "passive+no_connect"))
    )
    (net (code "106") (name "unconnected-(P9-HDMI_CLK{slash}GPIO3_21{slash}MCASP0_AHCLKX{slash}EQEP0_STROBE{slash}MCASP0_AXR3-Pad25)") (class "Default")
      (node (ref "P9") (pin "25") (pinfunction "HDMI_CLK/GPIO3_21/MCASP0_AHCLKX/EQEP0_STROBE/MCASP0_AXR3_25") (pintype "passive+no_connect"))
    )
    (net (code "107") (name "unconnected-(P9-I2C1_SCL{slash}SPI0_CS0{slash}MMC2_SDWP{slash}I2C1_SCL-Pad17)") (class "Default")
      (node (ref "P9") (pin "17") (pinfunction "I2C1_SCL/SPI0_CS0/MMC2_SDWP/I2C1_SCL_17") (pintype "passive+no_connect"))
    )
    (net (code "108") (name "unconnected-(P9-I2C1_SDA{slash}SPI0_D1{slash}MMC2_SDWP-Pad18)") (class "Default")
      (node (ref "P9") (pin "18") (pinfunction "I2C1_SDA/SPI0_D1/MMC2_SDWP_18") (pintype "passive+no_connect"))
    )
    (net (code "109") (name "unconnected-(P9-PWR_BUT-Pad9)") (class "Default")
      (node (ref "P9") (pin "9") (pinfunction "PWR_BUT_9") (pintype "passive+no_connect"))
    )
    (net (code "110") (name "unconnected-(P9-UART1_RXD{slash}MMC1_SDWP{slash}DCAN1_TX-Pad26)") (class "Default")
      (node (ref "P9") (pin "26") (pinfunction "UART1_RXD/MMC1_SDWP/DCAN1_TX_26") (pintype "passive+no_connect"))
    )
    (net (code "111") (name "unconnected-(P9-UART1_TXD{slash}UART1_TXD{slash}MMC2_SDWP{slash}DCAN1_RX-Pad24)") (class "Default")
      (node (ref "P9") (pin "24") (pinfunction "UART1_TXD/UART1_TXD/MMC2_SDWP/DCAN1_RX_24") (pintype "passive+no_connect"))
    )
    (net (code "112") (name "unconnected-(P9-UART2_RXD{slash}SPI0_SCLK{slash}UART2_RXD{slash}I2C2_SDA-Pad22)") (class "Default")
      (node (ref "P9") (pin "22") (pinfunction "UART2_RXD/SPI0_SCLK/UART2_RXD/I2C2_SDA_22") (pintype "passive+no_connect"))
    )
    (net (code "113") (name "unconnected-(P9-UART2_TXD{slash}SPI0_D0{slash}UART2_TXD{slash}I2C2_SCL-Pad21)") (class "Default")
      (node (ref "P9") (pin "21") (pinfunction "UART2_TXD/SPI0_D0/UART2_TXD/I2C2_SCL_21") (pintype "passive+no_connect"))
    )
    (net (code "114") (name "unconnected-(P9-UART4_RXD{slash}GPMC_WAIT0{slash}MII2_CRS{slash}GPMC_CSN4-Pad11)") (class "Default")
      (node (ref "P9") (pin "11") (pinfunction "UART4_RXD/GPMC_WAIT0/MII2_CRS/GPMC_CSN4_11") (pintype "passive+no_connect"))
    )
    (net (code "115") (name "unconnected-(P9-UART4_TXD{slash}GPMC_WPM{slash}MII2_RXERR{slash}GPMC_CSN5-Pad13)") (class "Default")
      (node (ref "P9") (pin "13") (pinfunction "UART4_TXD/GPMC_WPM/MII2_RXERR/GPMC_CSN5_13") (pintype "passive+no_connect"))
    )
    (net (code "116") (name "unconnected-(P9-VDD_3V3-Pad3)") (class "Default")
      (node (ref "P9") (pin "3") (pinfunction "VDD_3V3_3") (pintype "passive+no_connect"))
    )
    (net (code "117") (name "unconnected-(P9-VDD_3V3-Pad4)") (class "Default")
      (node (ref "P9") (pin "4") (pinfunction "VDD_3V3_4") (pintype "passive+no_connect"))
    )
    (net (code "118") (name "unconnected-(P9-VDD_5V-Pad5)") (class "Default")
      (node (ref "P9") (pin "5") (pinfunction "VDD_5V_5") (pintype "passive+no_connect"))
    )
    (net (code "119") (name "unconnected-(P9-VDD_5V-Pad6)") (class "Default")
      (node (ref "P9") (pin "6") (pinfunction "VDD_5V_6") (pintype "passive+no_connect"))
    )
    (net (code "120") (name "unconnected-(P9-VDD_ADC-Pad32)") (class "Default")
      (node (ref "P9") (pin "32") (pinfunction "VDD_ADC_32") (pintype "passive+no_connect"))
    )
    (net (code "121") (name "unconnected-(PA-1-NC-PadA1)") (class "Default")
      (node (ref "PA-1") (pin "A1") (pinfunction "NC_A1") (pintype "passive+no_connect"))
    )
    (net (code "122") (name "unconnected-(PA-1-RST-PadA3)") (class "Default")
      (node (ref "PA-1") (pin "A3") (pinfunction "RST_A3") (pintype "passive"))
    )
    (net (code "123") (name "unconnected-(PA-1-VIN-PadA8)") (class "Default")
      (node (ref "PA-1") (pin "A8") (pinfunction "VIN_A8") (pintype "passive+no_connect"))
    )
    (net (code "124") (name "unconnected-(PA-4-AREF-PadD8)") (class "Default")
      (node (ref "PA-4") (pin "D8") (pinfunction "AREF_D8") (pintype "passive+no_connect"))
    )
  )
)
